# 02_Top_Level.net
KiCad netlist of a schematic drawn in Altium Designer
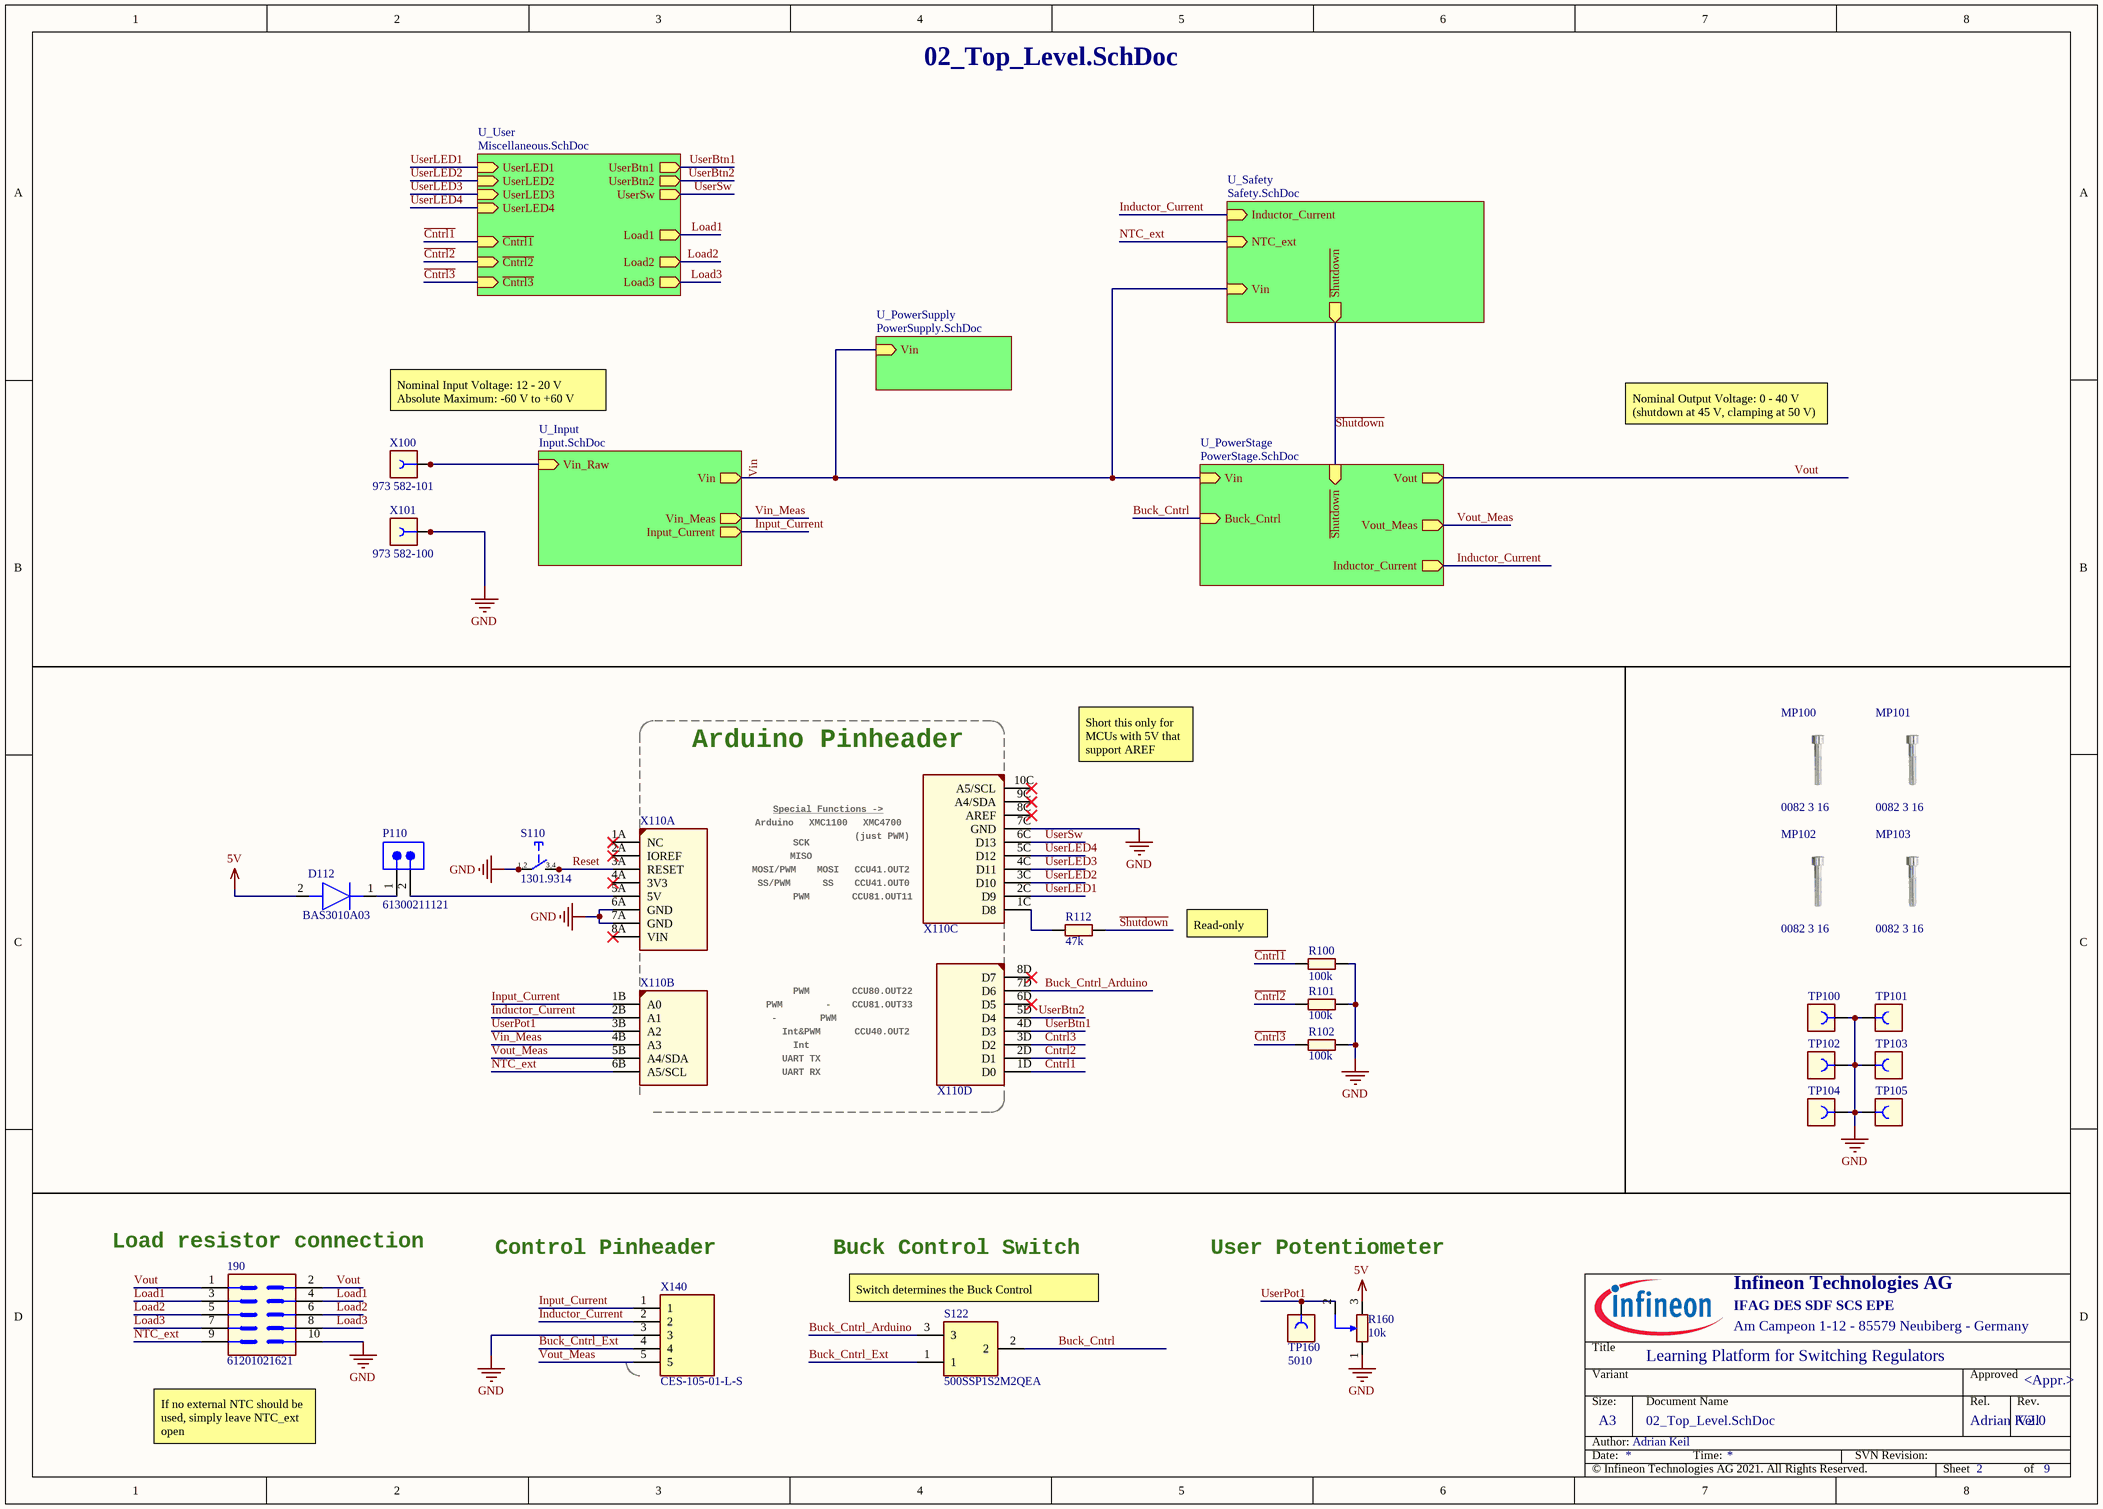
[diagram p0: 02_Top_Level.SchDoc]

(export (version "E")
  (design (tool "Eeschema 10.0.6"))
  (components
    (comp (ref "190")
      (value "61201021621")
      (footprint "CON-M-THT-61201021621")
      (description "WR-BHD Male Box Header, 2.54mm pitch, 10 pin, Vertical, Double row")
      (fields (field (name "MANUFACTURER") "Wurth Elektronik"))
      (libsource (lib "PCBLibraryData") (part "Header 5X2"))
    )
    (comp (ref "D112")
      (value "BAS3010A03")
      (footprint "myPcbLib:SOD2513X110N")
      (description "Diode")
      (fields
        (field (name "MANUFACTURER_PART_NUMBER") "BAS3010A03WE6327HTSA1")
        (field (name "MOUSER PART NUMBER") "726-BAS3010A-03WE6")
      )
      (libsource (lib "mySchlib") (part "BAS3010A03WE6327HTSA1"))
    )
    (comp (ref "MP100")
      (value "0082 3 16")
      (footprint "SCREW_0082 3 16_NPTH")
      (description "Cheese Head Screw With Hexagon Socket, DIN 912 (ISO 4762), M3, 16mm length")
      (fields
        (field (name "LEGACY PARTNUMBER") "MEC10000167")
        (field (name "MANUFACTURER") "Wurth Elektronik")
      )
      (libsource (lib "PCBLibraryData") (part "Screw_0082 3 16"))
    )
    (comp (ref "MP101")
      (value "0082 3 16")
      (footprint "SCREW_0082 3 16_NPTH")
      (description "Cheese Head Screw With Hexagon Socket, DIN 912 (ISO 4762), M3, 16mm length")
      (fields
        (field (name "LEGACY PARTNUMBER") "MEC10000167")
        (field (name "MANUFACTURER") "Wurth Elektronik")
      )
      (libsource (lib "PCBLibraryData") (part "Screw_0082 3 16"))
    )
    (comp (ref "MP102")
      (value "0082 3 16")
      (footprint "SCREW_0082 3 16_NPTH")
      (description "Cheese Head Screw With Hexagon Socket, DIN 912 (ISO 4762), M3, 16mm length")
      (fields
        (field (name "LEGACY PARTNUMBER") "MEC10000167")
        (field (name "MANUFACTURER") "Wurth Elektronik")
      )
      (libsource (lib "PCBLibraryData") (part "Screw_0082 3 16"))
    )
    (comp (ref "MP103")
      (value "0082 3 16")
      (footprint "SCREW_0082 3 16_NPTH")
      (description "Cheese Head Screw With Hexagon Socket, DIN 912 (ISO 4762), M3, 16mm length")
      (fields
        (field (name "LEGACY PARTNUMBER") "MEC10000167")
        (field (name "MANUFACTURER") "Wurth Elektronik")
      )
      (libsource (lib "PCBLibraryData") (part "Screw_0082 3 16"))
    )
    (comp (ref "P110")
      (value "61300211121")
      (footprint "61300211121")
      (libsource (lib "Altium Content Vault") (part "Header_Male_1R_02P"))
    )
    (comp (ref "R100")
      (value "100k")
      (footprint "RESC3216X60N")
      (description "RES / STD / 100k / 250mW / 1% / 100ppm/K / -55°C to 155°C / 1206(3216) / SMD / -")
      (fields (field (name "LEGACY PARTNUMBER") "RES01802971") (field (name "MANUFACTURER") "Vishay"))
      (libsource (lib "") (part "RES-SGL-STD-02P_00000006_1"))
    )
    (comp (ref "R101")
      (value "100k")
      (footprint "RESC3216X60N")
      (description "RES / STD / 100k / 250mW / 1% / 100ppm/K / -55°C to 155°C / 1206(3216) / SMD / -")
      (fields (field (name "LEGACY PARTNUMBER") "RES01802971") (field (name "MANUFACTURER") "Vishay"))
      (libsource (lib "") (part "RES-SGL-STD-02P_00000006_1"))
    )
    (comp (ref "R102")
      (value "100k")
      (footprint "RESC3216X60N")
      (description "RES / STD / 100k / 250mW / 1% / 100ppm/K / -55°C to 155°C / 1206(3216) / SMD / -")
      (fields (field (name "LEGACY PARTNUMBER") "RES01802971") (field (name "MANUFACTURER") "Vishay"))
      (libsource (lib "") (part "RES-SGL-STD-02P_00000006_1"))
    )
    (comp (ref "R112")
      (value "47k")
      (footprint "RESC3216X60N")
      (description "RES / STD / 47k / 250mW / 1% / 100ppm/K / -55°C to 155°C / 1206(3216) / SMD / -")
      (fields (field (name "LEGACY PARTNUMBER") "RES01802933") (field (name "MANUFACTURER") "Vishay"))
      (libsource (lib "PCBLibraryData") (part "RES-SGL-STD-02P_00000006"))
    )
    (comp (ref "R160")
      (value "10k")
      (footprint "POT-THT-3362P")
      (fields
        (field (name "MANUFACTURER") "Bourns")
        (field (name "LCSC PART #") "C6807374")
        (field (name "MPN") "3362P-1-103TLF")
      )
      (libsource (lib "PCBLibraryData") (part "RES-SGL-VAR-03P_00000026"))
    )
    (comp (ref "S110")
      (value "1301.9314")
      (footprint "SW-SMD-1301.9314")
      (description "Pushbutton Tactile Switch, Single Pole Single Throw, 4 Pins")
      (fields (field (name "LEGACY PARTNUMBER") "CON01500305") (field (name "MANUFACTURER") "Schurter"))
      (libsource (lib "PCBLibraryData") (part "sw_sr_no12_34_4p"))
    )
    (comp (ref "S122")
      (value "500SSP1S2M2QEA")
      (footprint "500SSP1S2M2QEA")
      (description "Connector")
      (fields (field (name "MOUSER PART NUMBER") "612-500SSP1S2M2QEA"))
      (libsource (lib "mySchlib") (part "500SSP1S2M2QEA"))
    )
    (comp (ref "TP100")
      (value "5011")
      (footprint "CON-THT-TP-5011")
      (description "PC Test Point-Multipurpose THT, Black")
      (fields
        (field (name "LEGACY PARTNUMBER") "CON01500530")
        (field (name "MANUFACTURER") "Keystone Electronics Corp.")
      )
      (libsource (lib "") (part "connector_1_f_1"))
    )
    (comp (ref "TP101")
      (value "5011")
      (footprint "CON-THT-TP-5011")
      (description "PC Test Point-Multipurpose THT, Black")
      (fields
        (field (name "LEGACY PARTNUMBER") "CON01500530")
        (field (name "MANUFACTURER") "Keystone Electronics Corp.")
      )
      (libsource (lib "PCBLibraryData") (part "connector_1_f"))
    )
    (comp (ref "TP102")
      (value "5011")
      (footprint "CON-THT-TP-5011")
      (description "PC Test Point-Multipurpose THT, Black")
      (fields
        (field (name "LEGACY PARTNUMBER") "CON01500530")
        (field (name "MANUFACTURER") "Keystone Electronics Corp.")
      )
      (libsource (lib "") (part "connector_1_f_1"))
    )
    (comp (ref "TP103")
      (value "5011")
      (footprint "CON-THT-TP-5011")
      (description "PC Test Point-Multipurpose THT, Black")
      (fields
        (field (name "LEGACY PARTNUMBER") "CON01500530")
        (field (name "MANUFACTURER") "Keystone Electronics Corp.")
      )
      (libsource (lib "PCBLibraryData") (part "connector_1_f"))
    )
    (comp (ref "TP104")
      (value "5011")
      (footprint "CON-THT-TP-5011")
      (description "PC Test Point-Multipurpose THT, Black")
      (fields
        (field (name "LEGACY PARTNUMBER") "CON01500530")
        (field (name "MANUFACTURER") "Keystone Electronics Corp.")
      )
      (libsource (lib "") (part "connector_1_f_1"))
    )
    (comp (ref "TP105")
      (value "5011")
      (footprint "CON-THT-TP-5011")
      (description "PC Test Point-Multipurpose THT, Black")
      (fields
        (field (name "LEGACY PARTNUMBER") "CON01500530")
        (field (name "MANUFACTURER") "Keystone Electronics Corp.")
      )
      (libsource (lib "PCBLibraryData") (part "connector_1_f"))
    )
    (comp (ref "TP160")
      (value "5010")
      (footprint "CON-THT-TP-5010")
      (description "PC Test Point-Multipurpose THT, Red")
      (fields
        (field (name "LEGACY PARTNUMBER") "CON01500529")
        (field (name "MANUFACTURER") "Keystone Electronics Corp.")
      )
      (libsource (lib "") (part "connector_1_f_2"))
    )
    (comp (ref "X100")
      (value "973 582-101")
      (footprint "CON-THT-973 582- 101")
      (description "Banana Socket, Red, 17.5mm Pitch")
      (fields
        (field (name "LEGACY PARTNUMBER") "CON01500041")
        (field (name "MANUFACTURER") "Hirschmann Test & Measurement")
      )
      (libsource (lib "PCBLibraryData") (part "soc_banana_2p"))
    )
    (comp (ref "X101")
      (value "973 582-100")
      (footprint "CON-THT-973 582- 100")
      (description "Banana Socket, black, 17.5mm Pitch")
      (fields
        (field (name "LEGACY PARTNUMBER") "CON01500045")
        (field (name "MANUFACTURER") "Hirschmann Test & Measurement")
      )
      (libsource (lib "PCBLibraryData") (part "soc_banana_2p"))
    )
    (comp (ref "X110")
      (value "Arduino-Uno")
      (footprint "Arduino-Uno")
      (description "Arduino Uno is a microcontroller board based on the ATmega328P")
      (fields (field (name "MANUFACTURER") "Infineon Technologies"))
      (libsource (lib "") (part "Arduino-Uno_1"))
    )
    (comp (ref "X140")
      (value "CES-105-01-L-S")
      (footprint "myPcbLib:CES-105-XX-Y-S")
      (description "Connector")
      (libsource (lib "mySchlib") (part "CES-105-01-L-S"))
    )
  )
  (nets
    (net (code "1") (name "/Buck_Cntrl") (class "Default")
      (node (ref "S122") (pin "2") (pinfunction "2_2") (pintype "passive"))
    )
    (net (code "2") (name "/Buck_Cntrl_Arduino") (class "Default")
      (node (ref "S122") (pin "3") (pinfunction "3_3") (pintype "passive"))
      (node (ref "X110") (pin "7D") (pinfunction "D6_7D") (pintype "passive"))
    )
    (net (code "3") (name "/Buck_Cntrl_Ext") (class "Default")
      (node (ref "S122") (pin "1") (pinfunction "1_1") (pintype "passive"))
      (node (ref "X140") (pin "4") (pinfunction "4_4") (pintype "passive"))
    )
    (net (code "4") (name "/Cntrl1") (class "Default")
      (node (ref "R100") (pin "1") (pinfunction "1_1") (pintype "passive"))
      (node (ref "X110") (pin "1D") (pinfunction "D0_1D") (pintype "passive"))
    )
    (net (code "5") (name "/Cntrl2") (class "Default")
      (node (ref "R101") (pin "1") (pinfunction "1_1") (pintype "passive"))
      (node (ref "X110") (pin "2D") (pinfunction "D1_2D") (pintype "passive"))
    )
    (net (code "6") (name "/Cntrl3") (class "Default")
      (node (ref "R102") (pin "1") (pinfunction "1_1") (pintype "passive"))
      (node (ref "X110") (pin "3D") (pinfunction "D2_3D") (pintype "passive"))
    )
    (net (code "7") (name "/Inductor_Current") (class "Default")
      (node (ref "X110") (pin "2B") (pinfunction "A1_2B") (pintype "passive"))
      (node (ref "X140") (pin "2") (pinfunction "2_2") (pintype "passive"))
    )
    (net (code "8") (name "/Input_Current") (class "Default")
      (node (ref "X110") (pin "1B") (pinfunction "A0_1B") (pintype "passive"))
      (node (ref "X140") (pin "1") (pinfunction "1_1") (pintype "passive"))
    )
    (net (code "9") (name "/Load1") (class "Default")
      (node (ref "190") (pin "3") (pinfunction "3_3") (pintype "passive"))
      (node (ref "190") (pin "4") (pinfunction "4_4") (pintype "passive"))
    )
    (net (code "10") (name "/Load2") (class "Default")
      (node (ref "190") (pin "5") (pinfunction "5_5") (pintype "passive"))
      (node (ref "190") (pin "6") (pinfunction "6_6") (pintype "passive"))
    )
    (net (code "11") (name "/Load3") (class "Default")
      (node (ref "190") (pin "7") (pinfunction "7_7") (pintype "passive"))
      (node (ref "190") (pin "8") (pinfunction "8_8") (pintype "passive"))
    )
    (net (code "12") (name "/NTC_ext") (class "Default")
      (node (ref "190") (pin "9") (pinfunction "9_9") (pintype "passive"))
      (node (ref "X110") (pin "6B") (pinfunction "A5/SCL_6B") (pintype "passive"))
    )
    (net (code "13") (name "/Reset") (class "Default")
      (node (ref "S110") (pin "3") (pinfunction "3_3") (pintype "passive"))
      (node (ref "S110") (pin "4") (pinfunction "4_4") (pintype "passive"))
      (node (ref "X110") (pin "3A") (pinfunction "RESET_3A") (pintype "passive"))
    )
    (net (code "14") (name "/Shutdown") (class "Default")
      (node (ref "R112") (pin "1") (pinfunction "1_1") (pintype "passive"))
    )
    (net (code "15") (name "/UserBtn1") (class "Default")
      (node (ref "X110") (pin "4D") (pinfunction "D3_4D") (pintype "passive"))
    )
    (net (code "16") (name "/UserBtn2") (class "Default")
      (node (ref "X110") (pin "5D") (pinfunction "D4_5D") (pintype "passive"))
    )
    (net (code "17") (name "/UserLED1") (class "Default")
      (node (ref "X110") (pin "2C") (pinfunction "D9_2C") (pintype "passive"))
    )
    (net (code "18") (name "/UserLED2") (class "Default")
      (node (ref "X110") (pin "3C") (pinfunction "D10_3C") (pintype "passive"))
    )
    (net (code "19") (name "/UserLED3") (class "Default")
      (node (ref "X110") (pin "4C") (pinfunction "D11_4C") (pintype "passive"))
    )
    (net (code "20") (name "/UserLED4") (class "Default")
      (node (ref "X110") (pin "5C") (pinfunction "D12_5C") (pintype "passive"))
    )
    (net (code "21") (name "/UserPot1") (class "Default")
      (node (ref "R160") (pin "2") (pinfunction "2_2") (pintype "passive"))
      (node (ref "TP160") (pin "1") (pinfunction "1_1") (pintype "passive"))
      (node (ref "X110") (pin "3B") (pinfunction "A2_3B") (pintype "passive"))
    )
    (net (code "22") (name "/UserSw") (class "Default")
      (node (ref "X110") (pin "6C") (pinfunction "D13_6C") (pintype "passive"))
    )
    (net (code "24") (name "/Vin_Meas") (class "Default")
      (node (ref "X110") (pin "4B") (pinfunction "A3_4B") (pintype "passive"))
    )
    (net (code "25") (name "/Vin_Raw") (class "Default")
      (node (ref "X100") (pin "1") (pinfunction "1_1") (pintype "passive"))
      (node (ref "X100") (pin "2") (pinfunction "2_2") (pintype "passive"))
    )
    (net (code "26") (name "/Vout") (class "Default")
      (node (ref "190") (pin "1") (pinfunction "1_1") (pintype "passive"))
      (node (ref "190") (pin "2") (pinfunction "2_2") (pintype "passive"))
    )
    (net (code "27") (name "/Vout_Meas") (class "Default")
      (node (ref "X110") (pin "5B") (pinfunction "A4/SDA_5B") (pintype "passive"))
      (node (ref "X140") (pin "5") (pinfunction "5_5") (pintype "passive"))
    )
    (net (code "28") (name "5V") (class "Default")
      (node (ref "D112") (pin "2") (pinfunction "A_2") (pintype "passive"))
      (node (ref "R160") (pin "3") (pinfunction "3_3") (pintype "passive"))
    )
    (net (code "29") (name "GND") (class "Default")
      (node (ref "190") (pin "10") (pinfunction "10_10") (pintype "passive"))
      (node (ref "R100") (pin "2") (pinfunction "2_2") (pintype "passive"))
      (node (ref "R101") (pin "2") (pinfunction "2_2") (pintype "passive"))
      (node (ref "R102") (pin "2") (pinfunction "2_2") (pintype "passive"))
      (node (ref "R160") (pin "1") (pinfunction "1_1") (pintype "passive"))
      (node (ref "S110") (pin "1") (pinfunction "1_1") (pintype "passive"))
      (node (ref "S110") (pin "2") (pinfunction "2_2") (pintype "passive"))
      (node (ref "TP100") (pin "1") (pinfunction "1_1") (pintype "passive"))
      (node (ref "TP101") (pin "1") (pinfunction "1_1") (pintype "passive"))
      (node (ref "TP102") (pin "1") (pinfunction "1_1") (pintype "passive"))
      (node (ref "TP103") (pin "1") (pinfunction "1_1") (pintype "passive"))
      (node (ref "TP104") (pin "1") (pinfunction "1_1") (pintype "passive"))
      (node (ref "TP105") (pin "1") (pinfunction "1_1") (pintype "passive"))
      (node (ref "X101") (pin "1") (pinfunction "1_1") (pintype "passive"))
      (node (ref "X101") (pin "2") (pinfunction "2_2") (pintype "passive"))
      (node (ref "X110") (pin "6A") (pinfunction "GND_6A") (pintype "passive"))
      (node (ref "X110") (pin "7A") (pinfunction "GND_7A") (pintype "passive"))
      (node (ref "X110") (pin "7C") (pinfunction "GND_7C") (pintype "passive"))
      (node (ref "X140") (pin "3") (pinfunction "3_3") (pintype "passive"))
    )
    (net (code "30") (name "Net-(D112-K)") (class "Default")
      (node (ref "D112") (pin "1") (pinfunction "K_1") (pintype "passive"))
      (node (ref "P110") (pin "1") (pinfunction "1_1") (pintype "passive"))
    )
    (net (code "31") (name "Net-(X110A-5V)") (class "Default")
      (node (ref "P110") (pin "2") (pinfunction "2_2") (pintype "passive"))
      (node (ref "X110") (pin "5A") (pinfunction "5V_5A") (pintype "passive"))
    )
    (net (code "32") (name "Net-(X110C-D8)") (class "Default")
      (node (ref "R112") (pin "2") (pinfunction "2_2") (pintype "passive"))
      (node (ref "X110") (pin "1C") (pinfunction "D8_1C") (pintype "passive"))
    )
    (net (code "33") (name "unconnected-(X110A-3V3-Pad4A)") (class "Default")
      (node (ref "X110") (pin "4A") (pinfunction "3V3_4A") (pintype "passive+no_connect"))
    )
    (net (code "34") (name "unconnected-(X110A-IOREF-Pad2A)") (class "Default")
      (node (ref "X110") (pin "2A") (pinfunction "IOREF_2A") (pintype "passive+no_connect"))
    )
    (net (code "35") (name "unconnected-(X110A-NC-Pad1A)") (class "Default")
      (node (ref "X110") (pin "1A") (pinfunction "NC_1A") (pintype "passive+no_connect"))
    )
    (net (code "36") (name "unconnected-(X110A-VIN-Pad8A)") (class "Default")
      (node (ref "X110") (pin "8A") (pinfunction "VIN_8A") (pintype "passive+no_connect"))
    )
    (net (code "37") (name "unconnected-(X110C-A4{slash}SDA-Pad9C)") (class "Default")
      (node (ref "X110") (pin "9C") (pinfunction "A4/SDA_9C") (pintype "passive+no_connect"))
    )
    (net (code "38") (name "unconnected-(X110C-A5{slash}SCL-Pad10C)") (class "Default")
      (node (ref "X110") (pin "10C") (pinfunction "A5/SCL_10C") (pintype "passive+no_connect"))
    )
    (net (code "39") (name "unconnected-(X110C-AREF-Pad8C)") (class "Default")
      (node (ref "X110") (pin "8C") (pinfunction "AREF_8C") (pintype "passive+no_connect"))
    )
    (net (code "40") (name "unconnected-(X110D-D5-Pad6D)") (class "Default")
      (node (ref "X110") (pin "6D") (pinfunction "D5_6D") (pintype "passive+no_connect"))
    )
    (net (code "41") (name "unconnected-(X110D-D7-Pad8D)") (class "Default")
      (node (ref "X110") (pin "8D") (pinfunction "D7_8D") (pintype "passive+no_connect"))
    )
  )
)
